# Sheet4_Switch.net
KiCad netlist of a schematic drawn in Altium Designer
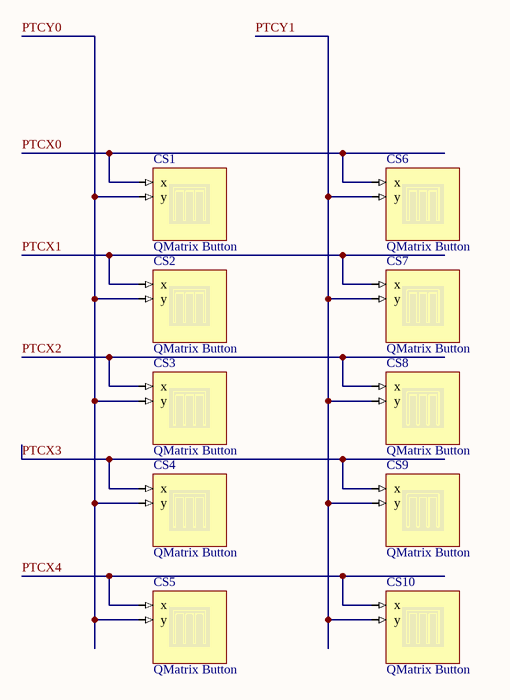
[diagram p0: Sheet4_Switch.SchDoc]

(export (version "E")
  (design (tool "Eeschema 10.0.6"))
  (components
    (comp (ref "CS1")
      (value "QMatrix Button")
      (footprint "qtouchsw")
      (libsource (lib "lightshow") (part "QMatrixButton"))
    )
    (comp (ref "CS2")
      (value "QMatrix Button")
      (footprint "qtouchsw")
      (libsource (lib "lightshow") (part "QMatrixButton"))
    )
    (comp (ref "CS3")
      (value "QMatrix Button")
      (footprint "qtouchsw")
      (libsource (lib "lightshow") (part "QMatrixButton"))
    )
    (comp (ref "CS4")
      (value "QMatrix Button")
      (footprint "qtouchsw")
      (libsource (lib "lightshow") (part "QMatrixButton"))
    )
    (comp (ref "CS5")
      (value "QMatrix Button")
      (footprint "qtouchsw")
      (libsource (lib "lightshow") (part "QMatrixButton"))
    )
    (comp (ref "CS6")
      (value "QMatrix Button")
      (footprint "qtouchsw")
      (libsource (lib "lightshow") (part "QMatrixButton"))
    )
    (comp (ref "CS7")
      (value "QMatrix Button")
      (footprint "qtouchsw")
      (libsource (lib "lightshow") (part "QMatrixButton"))
    )
    (comp (ref "CS8")
      (value "QMatrix Button")
      (footprint "qtouchsw")
      (libsource (lib "lightshow") (part "QMatrixButton"))
    )
    (comp (ref "CS9")
      (value "QMatrix Button")
      (footprint "qtouchsw")
      (libsource (lib "lightshow") (part "QMatrixButton"))
    )
    (comp (ref "CS10")
      (value "QMatrix Button")
      (footprint "qtouchsw")
      (libsource (lib "lightshow") (part "QMatrixButton"))
    )
  )
  (nets
    (net (code "1") (name "/PTCX0") (class "Default")
      (node (ref "CS1") (pin "x") (pinfunction "x_x") (pintype "input"))
      (node (ref "CS6") (pin "x") (pinfunction "x_x") (pintype "input"))
    )
    (net (code "2") (name "/PTCX1") (class "Default")
      (node (ref "CS2") (pin "x") (pinfunction "x_x") (pintype "input"))
      (node (ref "CS7") (pin "x") (pinfunction "x_x") (pintype "input"))
    )
    (net (code "3") (name "/PTCX2") (class "Default")
      (node (ref "CS3") (pin "x") (pinfunction "x_x") (pintype "input"))
      (node (ref "CS8") (pin "x") (pinfunction "x_x") (pintype "input"))
    )
    (net (code "4") (name "/PTCX3") (class "Default")
      (node (ref "CS4") (pin "x") (pinfunction "x_x") (pintype "input"))
      (node (ref "CS9") (pin "x") (pinfunction "x_x") (pintype "input"))
    )
    (net (code "5") (name "/PTCX4") (class "Default")
      (node (ref "CS10") (pin "x") (pinfunction "x_x") (pintype "input"))
      (node (ref "CS5") (pin "x") (pinfunction "x_x") (pintype "input"))
    )
    (net (code "6") (name "/PTCY0") (class "Default")
      (node (ref "CS1") (pin "y") (pinfunction "y_y") (pintype "input"))
      (node (ref "CS2") (pin "y") (pinfunction "y_y") (pintype "input"))
      (node (ref "CS3") (pin "y") (pinfunction "y_y") (pintype "input"))
      (node (ref "CS4") (pin "y") (pinfunction "y_y") (pintype "input"))
      (node (ref "CS5") (pin "y") (pinfunction "y_y") (pintype "input"))
    )
    (net (code "7") (name "/PTCY1") (class "Default")
      (node (ref "CS10") (pin "y") (pinfunction "y_y") (pintype "input"))
      (node (ref "CS6") (pin "y") (pinfunction "y_y") (pintype "input"))
      (node (ref "CS7") (pin "y") (pinfunction "y_y") (pintype "input"))
      (node (ref "CS8") (pin "y") (pinfunction "y_y") (pintype "input"))
      (node (ref "CS9") (pin "y") (pinfunction "y_y") (pintype "input"))
    )
  )
)
